# Current_Sensor.net
KiCad netlist of a schematic drawn in Altium Designer
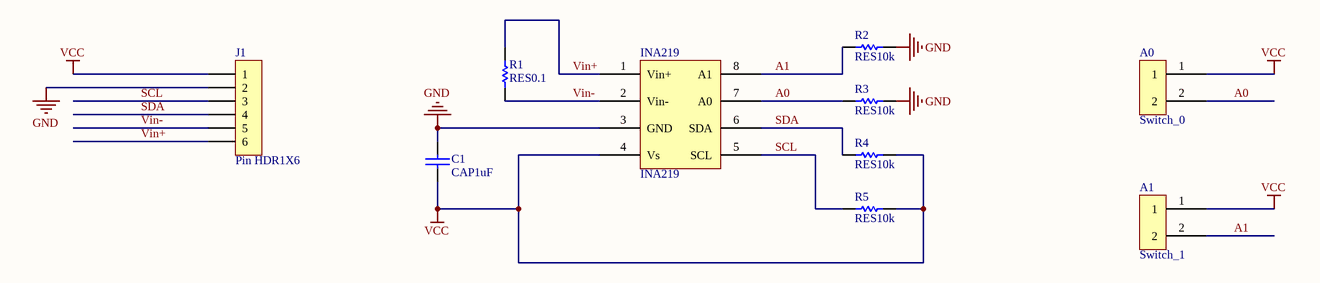
[diagram p0: Current Sensor.SchDoc]

(export (version "E")
  (design (tool "Eeschema 10.0.6"))
  (components
    (comp (ref "A0")
      (value "Switch_0")
      (footprint "TSOP65P180X145-2N")
      (libsource (lib "Lianxin_Library") (part "Component_1"))
    )
    (comp (ref "A1")
      (value "Switch_1")
      (footprint "TSOP65P180X145-2N")
      (libsource (lib "Lianxin_Library") (part "Component_1"))
    )
    (comp (ref "C1")
      (value "CAP1uF")
      (footprint "0603C")
      (description "无极性电容")
      (libsource (lib "电容") (part "CAP"))
    )
    (comp (ref "INA219") (value "INA219") (footprint "INA219") (libsource (lib "INA219") (part "INA219")))
    (comp (ref "J1")
      (value "Pin HDR1X6")
      (footprint "Pin HDR1X6/2.54mm-S")
      (libsource (lib "排针") (part "Pin HDR1X6"))
    )
    (comp (ref "R1") (value "RES0.1") (footprint "2512R") (libsource (lib "电阻") (part "RES")))
    (comp (ref "R2") (value "RES10k") (footprint "0603R") (libsource (lib "电阻") (part "RES")))
    (comp (ref "R3") (value "RES10k") (footprint "0603R") (libsource (lib "电阻") (part "RES")))
    (comp (ref "R4") (value "RES10k") (footprint "0603R") (libsource (lib "电阻") (part "RES")))
    (comp (ref "R5") (value "RES10k") (footprint "0603R") (libsource (lib "电阻") (part "RES")))
  )
  (nets
    (net (code "1") (name "/A0") (class "Default")
      (node (ref "A0") (pin "2") (pinfunction "2_2") (pintype "passive"))
      (node (ref "INA219") (pin "7") (pinfunction "A0_7") (pintype "passive"))
      (node (ref "R3") (pin "1") (pinfunction "1_1") (pintype "passive"))
    )
    (net (code "2") (name "/A1") (class "Default")
      (node (ref "A1") (pin "2") (pinfunction "2_2") (pintype "passive"))
      (node (ref "INA219") (pin "8") (pinfunction "A1_8") (pintype "passive"))
      (node (ref "R2") (pin "1") (pinfunction "1_1") (pintype "passive"))
    )
    (net (code "3") (name "/SCL") (class "Default")
      (node (ref "INA219") (pin "5") (pinfunction "SCL_5") (pintype "passive"))
      (node (ref "J1") (pin "3") (pinfunction "3_3") (pintype "passive"))
      (node (ref "R5") (pin "1") (pinfunction "1_1") (pintype "passive"))
    )
    (net (code "4") (name "/SDA") (class "Default")
      (node (ref "INA219") (pin "6") (pinfunction "SDA_6") (pintype "passive"))
      (node (ref "J1") (pin "4") (pinfunction "4_4") (pintype "passive"))
      (node (ref "R4") (pin "1") (pinfunction "1_1") (pintype "passive"))
    )
    (net (code "5") (name "/Vin+") (class "Default")
      (node (ref "INA219") (pin "1") (pinfunction "Vin+_1") (pintype "passive"))
      (node (ref "J1") (pin "6") (pinfunction "6_6") (pintype "passive"))
      (node (ref "R1") (pin "1") (pinfunction "1_1") (pintype "passive"))
    )
    (net (code "6") (name "/Vin-") (class "Default")
      (node (ref "INA219") (pin "2") (pinfunction "Vin-_2") (pintype "passive"))
      (node (ref "J1") (pin "5") (pinfunction "5_5") (pintype "passive"))
      (node (ref "R1") (pin "2") (pinfunction "2_2") (pintype "passive"))
    )
    (net (code "7") (name "GND") (class "Default")
      (node (ref "C1") (pin "2") (pinfunction "2_2") (pintype "passive"))
      (node (ref "INA219") (pin "3") (pinfunction "GND_3") (pintype "passive"))
      (node (ref "J1") (pin "2") (pinfunction "2_2") (pintype "passive"))
      (node (ref "R2") (pin "2") (pinfunction "2_2") (pintype "passive"))
      (node (ref "R3") (pin "2") (pinfunction "2_2") (pintype "passive"))
    )
    (net (code "8") (name "VCC") (class "Default")
      (node (ref "A0") (pin "1") (pinfunction "1_1") (pintype "passive"))
      (node (ref "A1") (pin "1") (pinfunction "1_1") (pintype "passive"))
      (node (ref "C1") (pin "1") (pinfunction "1_1") (pintype "passive"))
      (node (ref "INA219") (pin "4") (pinfunction "Vs_4") (pintype "passive"))
      (node (ref "J1") (pin "1") (pinfunction "1_1") (pintype "passive"))
      (node (ref "R4") (pin "2") (pinfunction "2_2") (pintype "passive"))
      (node (ref "R5") (pin "2") (pinfunction "2_2") (pintype "passive"))
    )
  )
)
